# GasSensorCentralButtons_v1_0.net
KiCad netlist of a schematic drawn in EAGLE
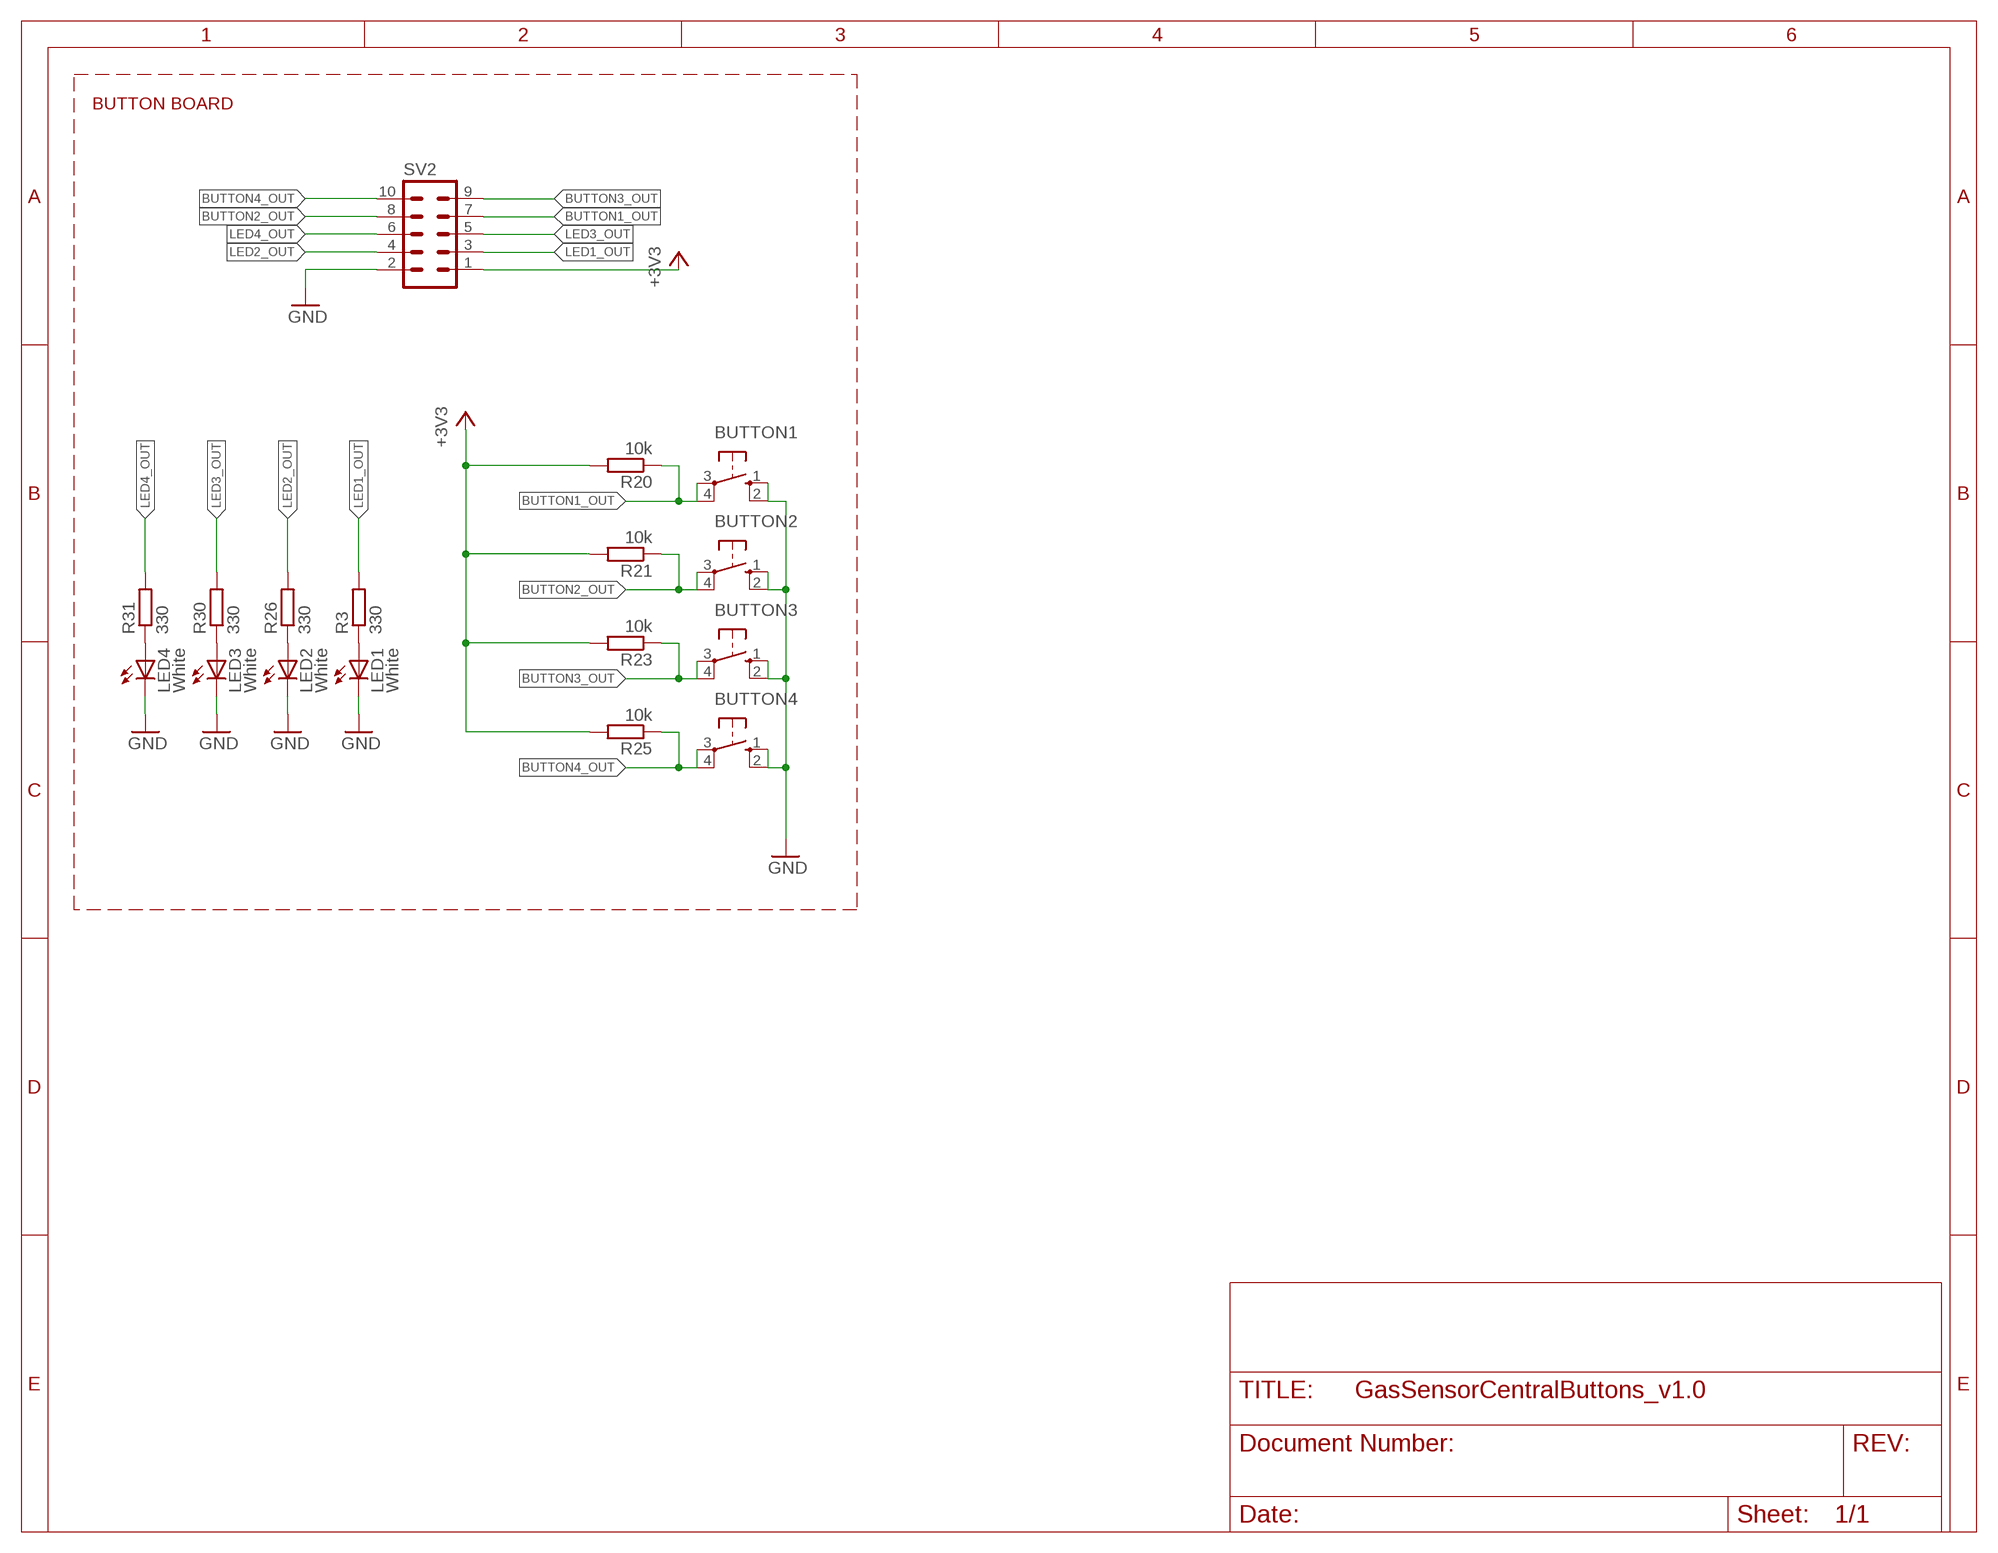
[diagram p0: schematic, sheet 1]

(export (version "E")
  (design (tool "Eeschema 10.0.6"))
  (components
    (comp (ref "BUTTON1")
      (value "10-XX")
      (footprint "eagle-import:B3F-10XX")
      (fields (field (name "MPN") "B3F-1000"))
      (libsource (lib "eagle-import") (part "10-XX"))
    )
    (comp (ref "BUTTON2")
      (value "10-XX")
      (footprint "eagle-import:B3F-10XX")
      (fields (field (name "MPN") "B3F-1000"))
      (libsource (lib "eagle-import") (part "10-XX"))
    )
    (comp (ref "BUTTON3")
      (value "10-XX")
      (footprint "eagle-import:B3F-10XX")
      (fields (field (name "MPN") "B3F-1000"))
      (libsource (lib "eagle-import") (part "10-XX"))
    )
    (comp (ref "BUTTON4")
      (value "10-XX")
      (footprint "eagle-import:B3F-10XX")
      (fields (field (name "MPN") "B3F-1000"))
      (libsource (lib "eagle-import") (part "10-XX"))
    )
    (comp (ref "LED1")
      (value "White")
      (footprint "eagle-import:LED3MM")
      (libsource (lib "eagle-import") (part "LED3MM"))
    )
    (comp (ref "LED2")
      (value "White")
      (footprint "eagle-import:LED3MM")
      (libsource (lib "eagle-import") (part "LED3MM"))
    )
    (comp (ref "LED3")
      (value "White")
      (footprint "eagle-import:LED3MM")
      (libsource (lib "eagle-import") (part "LED3MM"))
    )
    (comp (ref "LED4")
      (value "White")
      (footprint "eagle-import:LED3MM")
      (libsource (lib "eagle-import") (part "LED3MM"))
    )
    (comp (ref "R3")
      (value "330")
      (footprint "eagle-import:0207_10")
      (libsource (lib "eagle-import") (part "R-EU_0207/10"))
    )
    (comp (ref "R20")
      (value "10k")
      (footprint "eagle-import:0207_10")
      (libsource (lib "eagle-import") (part "R-EU_0207/10"))
    )
    (comp (ref "R21")
      (value "10k")
      (footprint "eagle-import:0207_10")
      (libsource (lib "eagle-import") (part "R-EU_0207/10"))
    )
    (comp (ref "R23")
      (value "10k")
      (footprint "eagle-import:0207_10")
      (libsource (lib "eagle-import") (part "R-EU_0207/10"))
    )
    (comp (ref "R25")
      (value "10k")
      (footprint "eagle-import:0207_10")
      (libsource (lib "eagle-import") (part "R-EU_0207/10"))
    )
    (comp (ref "R26")
      (value "330")
      (footprint "eagle-import:0207_10")
      (libsource (lib "eagle-import") (part "R-EU_0207/10"))
    )
    (comp (ref "R30")
      (value "330")
      (footprint "eagle-import:0207_10")
      (libsource (lib "eagle-import") (part "R-EU_0207/10"))
    )
    (comp (ref "R31")
      (value "330")
      (footprint "eagle-import:0207_10")
      (libsource (lib "eagle-import") (part "R-EU_0207/10"))
    )
    (comp (ref "SV2")
      (value "ML10")
      (footprint "eagle-import:ML10")
      (libsource (lib "eagle-import") (part "ML10"))
    )
  )
  (nets
    (net (code "1") (name "+3V3") (class "Default")
      (node (ref "R20") (pin "2") (pinfunction "2_2") (pintype "passive"))
      (node (ref "R21") (pin "2") (pinfunction "2_2") (pintype "passive"))
      (node (ref "R23") (pin "2") (pinfunction "2_2") (pintype "passive"))
      (node (ref "R25") (pin "2") (pinfunction "2_2") (pintype "passive"))
      (node (ref "SV2") (pin "1") (pinfunction "1_1") (pintype "passive"))
    )
    (net (code "2") (name "BUTTON1_OUT") (class "Default")
      (node (ref "BUTTON1") (pin "3") (pinfunction "P_3") (pintype "passive"))
      (node (ref "BUTTON1") (pin "4") (pinfunction "P1_4") (pintype "passive"))
      (node (ref "R20") (pin "1") (pinfunction "1_1") (pintype "passive"))
      (node (ref "SV2") (pin "7") (pinfunction "7_7") (pintype "passive"))
    )
    (net (code "3") (name "BUTTON2_OUT") (class "Default")
      (node (ref "BUTTON2") (pin "3") (pinfunction "P_3") (pintype "passive"))
      (node (ref "BUTTON2") (pin "4") (pinfunction "P1_4") (pintype "passive"))
      (node (ref "R21") (pin "1") (pinfunction "1_1") (pintype "passive"))
      (node (ref "SV2") (pin "8") (pinfunction "8_8") (pintype "passive"))
    )
    (net (code "4") (name "BUTTON3_OUT") (class "Default")
      (node (ref "BUTTON3") (pin "3") (pinfunction "P_3") (pintype "passive"))
      (node (ref "BUTTON3") (pin "4") (pinfunction "P1_4") (pintype "passive"))
      (node (ref "R23") (pin "1") (pinfunction "1_1") (pintype "passive"))
      (node (ref "SV2") (pin "9") (pinfunction "9_9") (pintype "passive"))
    )
    (net (code "5") (name "BUTTON4_OUT") (class "Default")
      (node (ref "BUTTON4") (pin "3") (pinfunction "P_3") (pintype "passive"))
      (node (ref "BUTTON4") (pin "4") (pinfunction "P1_4") (pintype "passive"))
      (node (ref "R25") (pin "1") (pinfunction "1_1") (pintype "passive"))
      (node (ref "SV2") (pin "10") (pinfunction "10_10") (pintype "passive"))
    )
    (net (code "6") (name "GND") (class "Default")
      (node (ref "BUTTON1") (pin "1") (pinfunction "S_1") (pintype "passive"))
      (node (ref "BUTTON1") (pin "2") (pinfunction "S1_2") (pintype "passive"))
      (node (ref "BUTTON2") (pin "1") (pinfunction "S_1") (pintype "passive"))
      (node (ref "BUTTON2") (pin "2") (pinfunction "S1_2") (pintype "passive"))
      (node (ref "BUTTON3") (pin "1") (pinfunction "S_1") (pintype "passive"))
      (node (ref "BUTTON3") (pin "2") (pinfunction "S1_2") (pintype "passive"))
      (node (ref "BUTTON4") (pin "1") (pinfunction "S_1") (pintype "passive"))
      (node (ref "BUTTON4") (pin "2") (pinfunction "S1_2") (pintype "passive"))
      (node (ref "LED1") (pin "K") (pinfunction "C_K") (pintype "passive"))
      (node (ref "LED2") (pin "K") (pinfunction "C_K") (pintype "passive"))
      (node (ref "LED3") (pin "K") (pinfunction "C_K") (pintype "passive"))
      (node (ref "LED4") (pin "K") (pinfunction "C_K") (pintype "passive"))
      (node (ref "SV2") (pin "2") (pinfunction "2_2") (pintype "passive"))
    )
    (net (code "7") (name "LED1_OUT") (class "Default")
      (node (ref "R3") (pin "2") (pinfunction "2_2") (pintype "passive"))
      (node (ref "SV2") (pin "3") (pinfunction "3_3") (pintype "passive"))
    )
    (net (code "8") (name "LED2_OUT") (class "Default")
      (node (ref "R26") (pin "2") (pinfunction "2_2") (pintype "passive"))
      (node (ref "SV2") (pin "4") (pinfunction "4_4") (pintype "passive"))
    )
    (net (code "9") (name "LED3_OUT") (class "Default")
      (node (ref "R30") (pin "2") (pinfunction "2_2") (pintype "passive"))
      (node (ref "SV2") (pin "5") (pinfunction "5_5") (pintype "passive"))
    )
    (net (code "10") (name "LED4_OUT") (class "Default")
      (node (ref "R31") (pin "2") (pinfunction "2_2") (pintype "passive"))
      (node (ref "SV2") (pin "6") (pinfunction "6_6") (pintype "passive"))
    )
    (net (code "11") (name "Net-(LED1-PadA)") (class "Default")
      (node (ref "LED1") (pin "A") (pinfunction "A_A") (pintype "passive"))
      (node (ref "R3") (pin "1") (pinfunction "1_1") (pintype "passive"))
    )
    (net (code "12") (name "Net-(LED2-PadA)") (class "Default")
      (node (ref "LED2") (pin "A") (pinfunction "A_A") (pintype "passive"))
      (node (ref "R26") (pin "1") (pinfunction "1_1") (pintype "passive"))
    )
    (net (code "13") (name "Net-(LED3-PadA)") (class "Default")
      (node (ref "LED3") (pin "A") (pinfunction "A_A") (pintype "passive"))
      (node (ref "R30") (pin "1") (pinfunction "1_1") (pintype "passive"))
    )
    (net (code "14") (name "Net-(LED4-PadA)") (class "Default")
      (node (ref "LED4") (pin "A") (pinfunction "A_A") (pintype "passive"))
      (node (ref "R31") (pin "1") (pinfunction "1_1") (pintype "passive"))
    )
  )
)
